# U2FHIDDevice_1.net
KiCad netlist of a schematic drawn in EAGLE
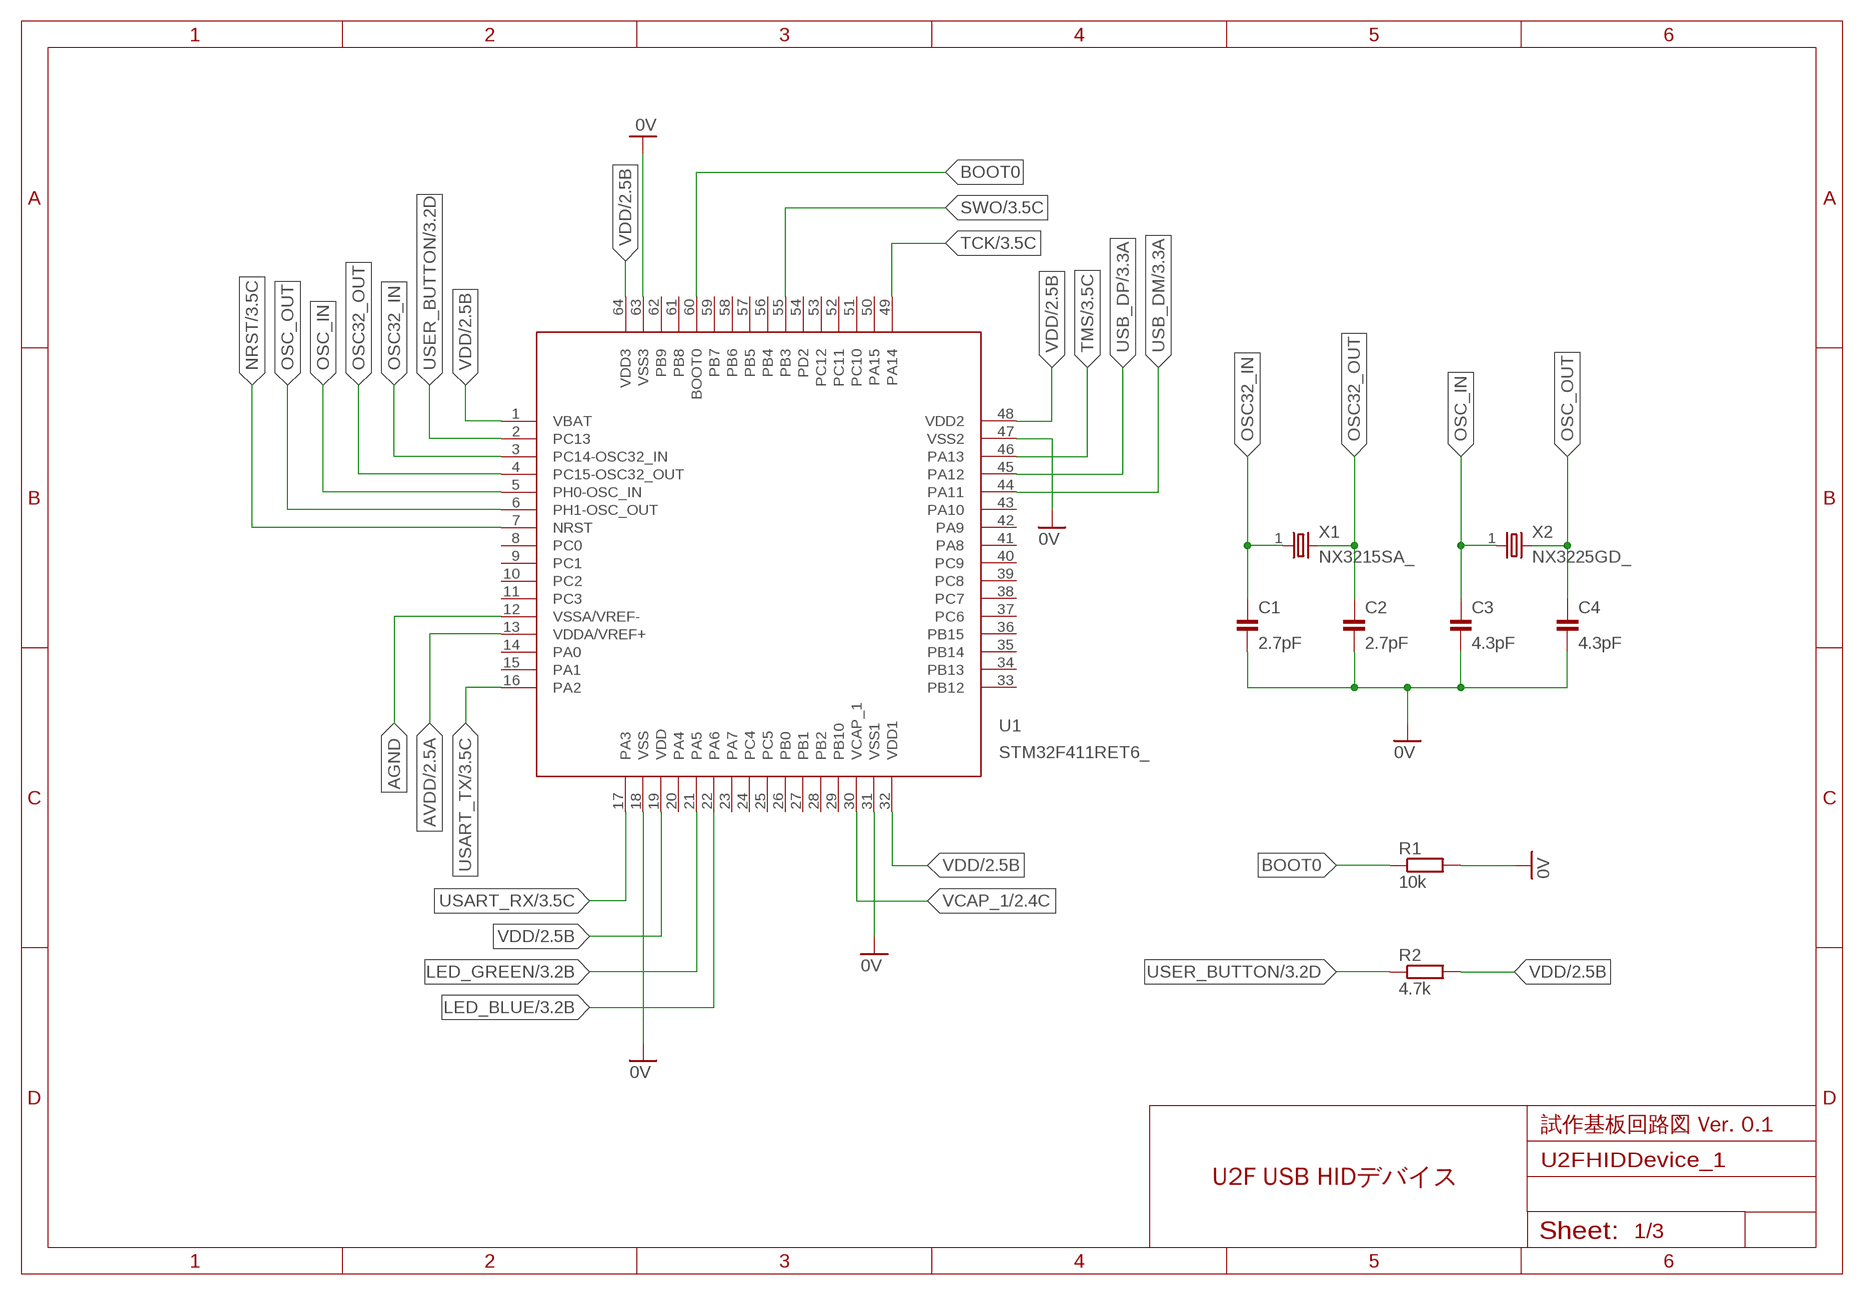
[diagram p0: schematic, sheet 1]
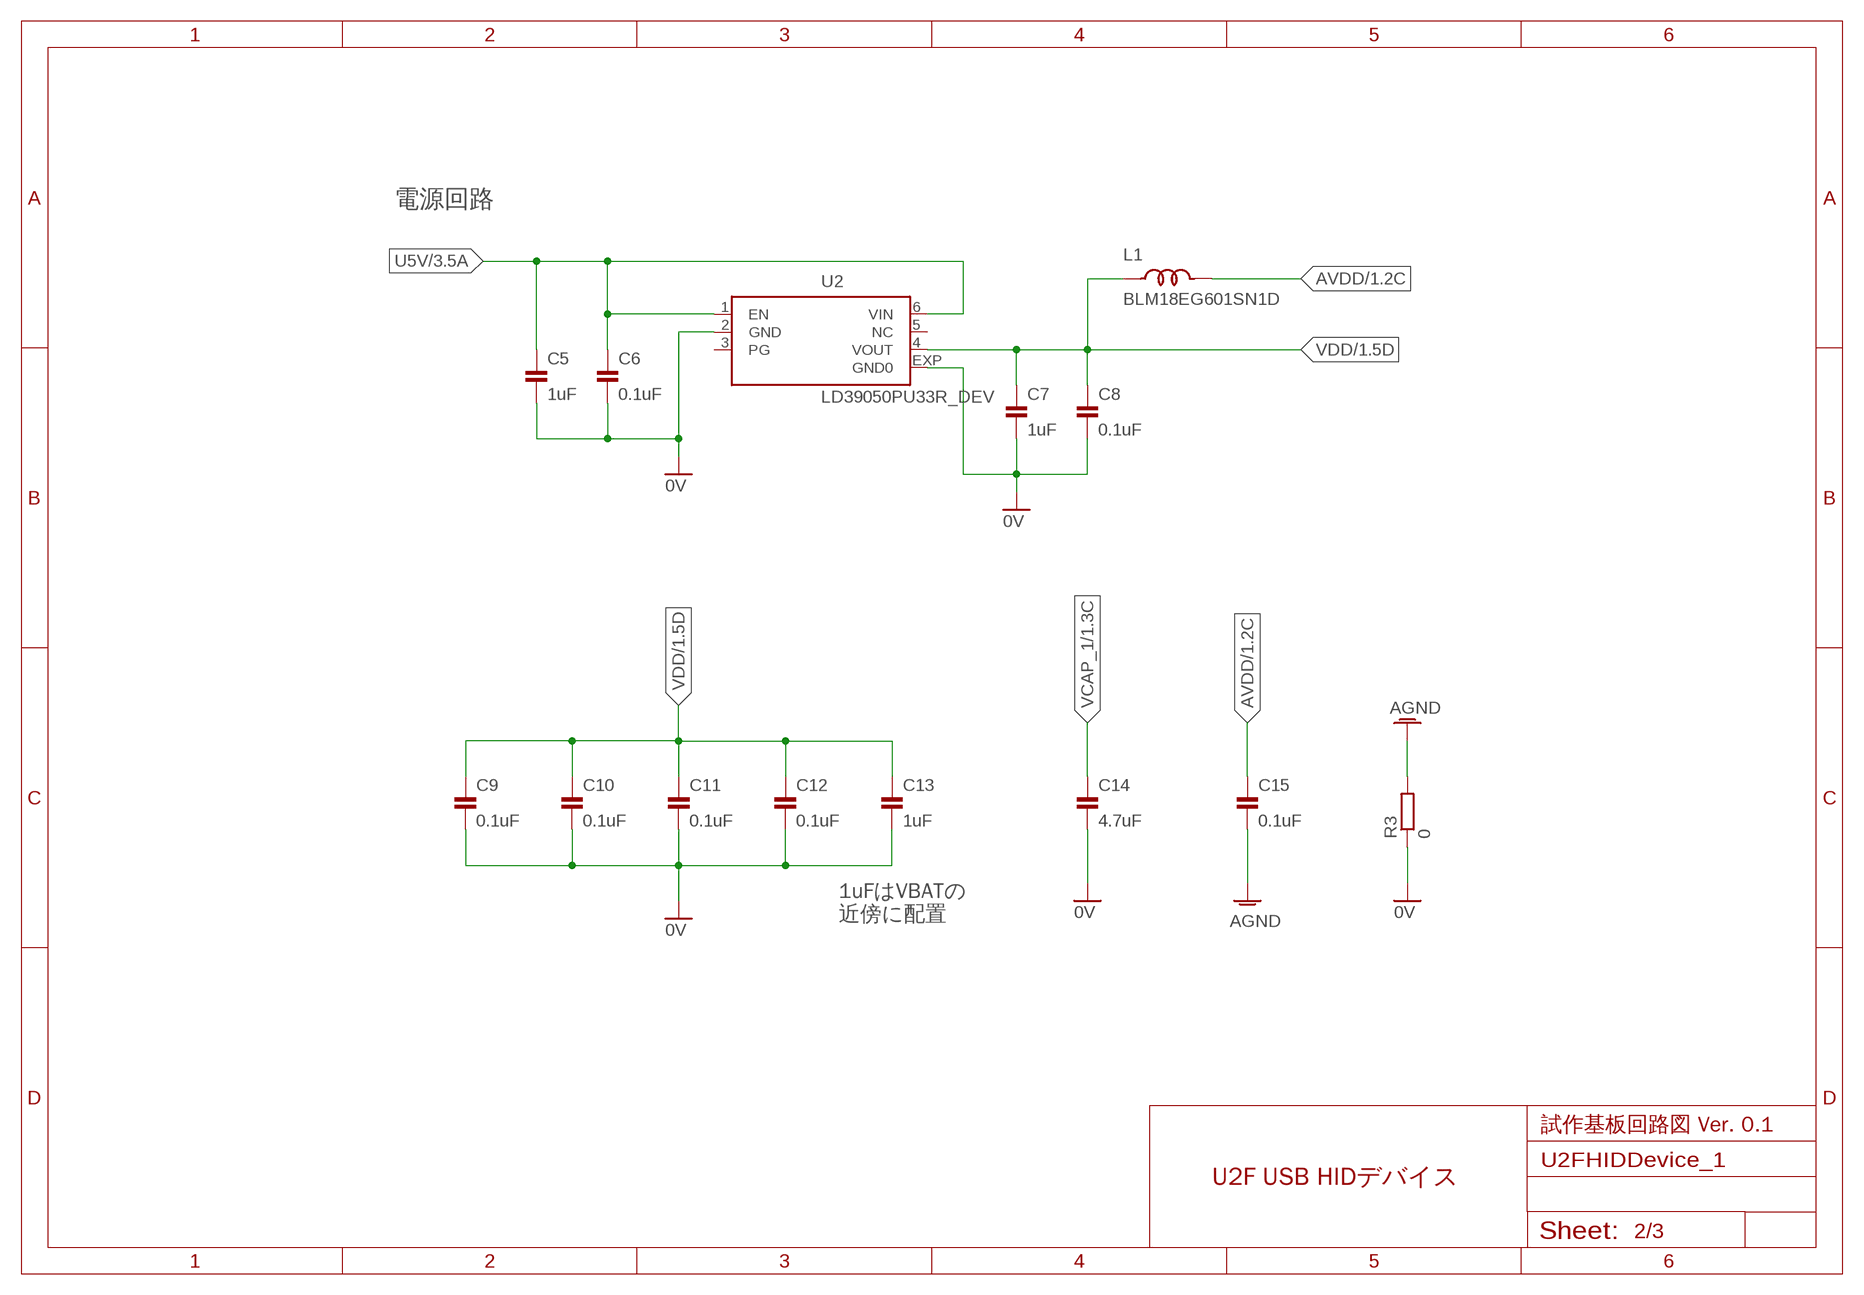
[diagram p1: schematic, sheet 2]
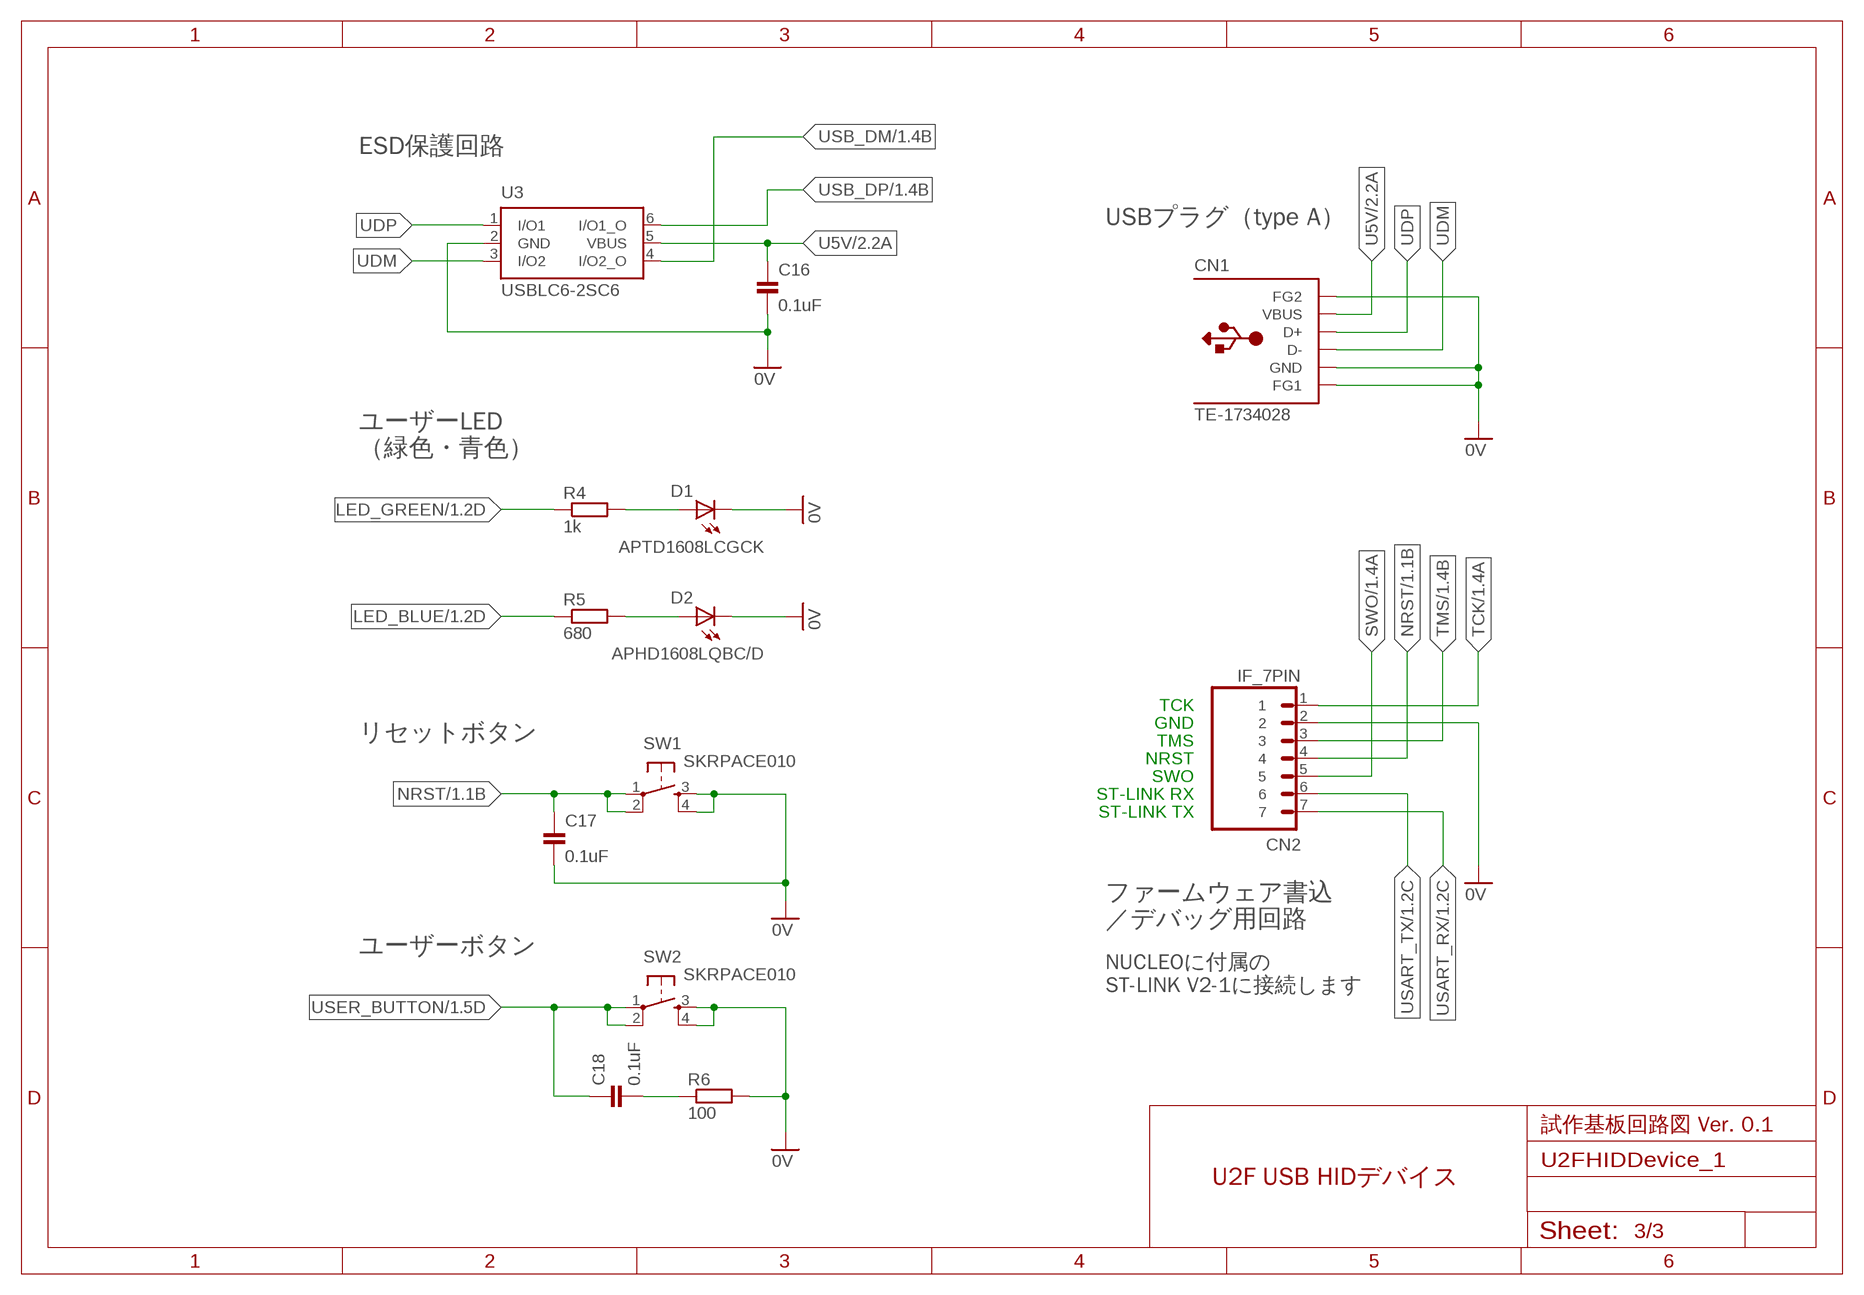
[diagram p2: schematic, sheet 3]

(export (version "E")
  (design (tool "Eeschema 10.0.6"))
  (components
    (comp (ref "C5")
      (value "1uF")
      (footprint "eagle-import:C0603K")
      (libsource (lib "eagle-import") (part "CAP_0603"))
    )
    (comp (ref "C6")
      (value "0.1uF")
      (footprint "eagle-import:C0603K")
      (libsource (lib "eagle-import") (part "CAP_0603"))
    )
    (comp (ref "C7")
      (value "1uF")
      (footprint "eagle-import:C0603K")
      (libsource (lib "eagle-import") (part "CAP_0603"))
    )
    (comp (ref "C8")
      (value "0.1uF")
      (footprint "eagle-import:C0603K")
      (libsource (lib "eagle-import") (part "CAP_0603"))
    )
    (comp (ref "C9")
      (value "0.1uF")
      (footprint "eagle-import:C0603K")
      (libsource (lib "eagle-import") (part "CAP_0603"))
    )
    (comp (ref "C10")
      (value "0.1uF")
      (footprint "eagle-import:C0603K")
      (libsource (lib "eagle-import") (part "CAP_0603"))
    )
    (comp (ref "C11")
      (value "0.1uF")
      (footprint "eagle-import:C0603K")
      (libsource (lib "eagle-import") (part "CAP_0603"))
    )
    (comp (ref "C12")
      (value "0.1uF")
      (footprint "eagle-import:C0603K")
      (libsource (lib "eagle-import") (part "CAP_0603"))
    )
    (comp (ref "C13")
      (value "1uF")
      (footprint "eagle-import:C0603K")
      (libsource (lib "eagle-import") (part "CAP_0603"))
    )
    (comp (ref "C14")
      (value "4.7uF")
      (footprint "eagle-import:C1206")
      (libsource (lib "eagle-import") (part "CAP_1206"))
    )
    (comp (ref "C15")
      (value "0.1uF")
      (footprint "eagle-import:C0603K")
      (libsource (lib "eagle-import") (part "CAP_0603"))
    )
    (comp (ref "L1")
      (value "BLM18EG601SN1D")
      (footprint "eagle-import:R0603")
      (libsource (lib "eagle-import") (part "BLM18EG601SN1D"))
    )
    (comp (ref "R3")
      (value "0")
      (footprint "eagle-import:R0603")
      (libsource (lib "eagle-import") (part "RESISTOR_0603"))
    )
    (comp (ref "U2")
      (value "LD39050PU33R_DEV")
      (footprint "eagle-import:DFN6-3X3_DEV")
      (libsource (lib "eagle-import") (part "LD39050PU33R_DEV"))
    )
    (comp (ref "C1")
      (value "2.7pF")
      (footprint "eagle-import:C0603K")
      (libsource (lib "eagle-import") (part "CAP_0603"))
    )
    (comp (ref "C2")
      (value "2.7pF")
      (footprint "eagle-import:C0603K")
      (libsource (lib "eagle-import") (part "CAP_0603"))
    )
    (comp (ref "C3")
      (value "4.3pF")
      (footprint "eagle-import:C0603K")
      (libsource (lib "eagle-import") (part "CAP_0603"))
    )
    (comp (ref "C4")
      (value "4.3pF")
      (footprint "eagle-import:C0603K")
      (libsource (lib "eagle-import") (part "CAP_0603"))
    )
    (comp (ref "R1")
      (value "10k")
      (footprint "eagle-import:R0603")
      (libsource (lib "eagle-import") (part "RESISTOR_0603"))
    )
    (comp (ref "R2")
      (value "4.7k")
      (footprint "eagle-import:R0603")
      (libsource (lib "eagle-import") (part "RESISTOR_0603"))
    )
    (comp (ref "U1")
      (value "STM32F411RET6_")
      (footprint "eagle-import:LQFP64-10X10_DEV")
      (libsource (lib "eagle-import") (part "STM32F411RET6_"))
    )
    (comp (ref "X1")
      (value "NX3215SA_")
      (footprint "eagle-import:NX3215_DEV")
      (libsource (lib "eagle-import") (part "NX3215SA_"))
    )
    (comp (ref "X2")
      (value "NX3225GD_")
      (footprint "eagle-import:NX3225_DEV")
      (libsource (lib "eagle-import") (part "NX3225GD_"))
    )
    (comp (ref "C16")
      (value "0.1uF")
      (footprint "eagle-import:C0603K")
      (libsource (lib "eagle-import") (part "CAP_0603"))
    )
    (comp (ref "C17")
      (value "0.1uF")
      (footprint "eagle-import:C0603K")
      (libsource (lib "eagle-import") (part "CAP_0603"))
    )
    (comp (ref "C18")
      (value "0.1uF")
      (footprint "eagle-import:C0603K")
      (libsource (lib "eagle-import") (part "CAP_0603"))
    )
    (comp (ref "CN1")
      (value "TE-1734028")
      (footprint "eagle-import:TE-1734028")
      (libsource (lib "eagle-import") (part "TE-1734028"))
    )
    (comp (ref "CN2")
      (value "IF_7PIN")
      (footprint "eagle-import:HEADER_7PIN")
      (libsource (lib "eagle-import") (part "IF_7PIN"))
    )
    (comp (ref "D1")
      (value "APTD1608LCGCK")
      (footprint "eagle-import:CHIPLED_0603")
      (libsource (lib "eagle-import") (part "APTD1608LCGCK"))
    )
    (comp (ref "D2")
      (value "APHD1608LQBC/D")
      (footprint "eagle-import:CHIPLED_0603")
      (libsource (lib "eagle-import") (part "APHD1608LQBC/D"))
    )
    (comp (ref "R4")
      (value "1k")
      (footprint "eagle-import:R0603")
      (libsource (lib "eagle-import") (part "RESISTOR_0603"))
    )
    (comp (ref "R5")
      (value "680")
      (footprint "eagle-import:R0603")
      (libsource (lib "eagle-import") (part "RESISTOR_0603"))
    )
    (comp (ref "R6")
      (value "100")
      (footprint "eagle-import:R0603")
      (libsource (lib "eagle-import") (part "RESISTOR_0603"))
    )
    (comp (ref "SW1")
      (value "SKRPACE010")
      (footprint "eagle-import:SKRPACE010")
      (libsource (lib "eagle-import") (part "SKRPACE010"))
    )
    (comp (ref "SW2")
      (value "SKRPACE010")
      (footprint "eagle-import:SKRPACE010")
      (libsource (lib "eagle-import") (part "SKRPACE010"))
    )
    (comp (ref "U3")
      (value "USBLC6-2SC6")
      (footprint "eagle-import:SOT23-6L")
      (libsource (lib "eagle-import") (part "USBLC6-2SC6"))
    )
  )
  (nets
    (net (code "1") (name "0V") (class "Default")
      (node (ref "C1") (pin "2") (pinfunction "2_2") (pintype "passive"))
      (node (ref "C10") (pin "2") (pinfunction "2_2") (pintype "passive"))
      (node (ref "C11") (pin "2") (pinfunction "2_2") (pintype "passive"))
      (node (ref "C12") (pin "2") (pinfunction "2_2") (pintype "passive"))
      (node (ref "C13") (pin "2") (pinfunction "2_2") (pintype "passive"))
      (node (ref "C14") (pin "2") (pinfunction "2_2") (pintype "passive"))
      (node (ref "C16") (pin "2") (pinfunction "2_2") (pintype "passive"))
      (node (ref "C17") (pin "2") (pinfunction "2_2") (pintype "passive"))
      (node (ref "C2") (pin "2") (pinfunction "2_2") (pintype "passive"))
      (node (ref "C3") (pin "2") (pinfunction "2_2") (pintype "passive"))
      (node (ref "C4") (pin "2") (pinfunction "2_2") (pintype "passive"))
      (node (ref "C5") (pin "2") (pinfunction "2_2") (pintype "passive"))
      (node (ref "C6") (pin "2") (pinfunction "2_2") (pintype "passive"))
      (node (ref "C7") (pin "2") (pinfunction "2_2") (pintype "passive"))
      (node (ref "C8") (pin "2") (pinfunction "2_2") (pintype "passive"))
      (node (ref "C9") (pin "2") (pinfunction "2_2") (pintype "passive"))
      (node (ref "CN1") (pin "FG1") (pinfunction "FG1_FG1") (pintype "passive"))
      (node (ref "CN1") (pin "FG2") (pinfunction "FG2_FG2") (pintype "passive"))
      (node (ref "CN1") (pin "P$4") (pinfunction "GND_P$4") (pintype "passive"))
      (node (ref "CN2") (pin "2") (pinfunction "2_2") (pintype "passive"))
      (node (ref "D1") (pin "C") (pinfunction "C_C") (pintype "passive"))
      (node (ref "D2") (pin "C") (pinfunction "C_C") (pintype "passive"))
      (node (ref "R1") (pin "2") (pinfunction "2_2") (pintype "passive"))
      (node (ref "R3") (pin "1") (pinfunction "1_1") (pintype "passive"))
      (node (ref "R6") (pin "2") (pinfunction "2_2") (pintype "passive"))
      (node (ref "SW1") (pin "3") (pinfunction "S_3") (pintype "passive"))
      (node (ref "SW1") (pin "4") (pinfunction "S1_4") (pintype "passive"))
      (node (ref "SW2") (pin "3") (pinfunction "S_3") (pintype "passive"))
      (node (ref "SW2") (pin "4") (pinfunction "S1_4") (pintype "passive"))
      (node (ref "U1") (pin "18") (pinfunction "VSS_18") (pintype "passive"))
      (node (ref "U1") (pin "31") (pinfunction "VSS1_31") (pintype "passive"))
      (node (ref "U1") (pin "47") (pinfunction "VSS2_47") (pintype "passive"))
      (node (ref "U1") (pin "63") (pinfunction "VSS3_63") (pintype "passive"))
      (node (ref "U2") (pin "2") (pinfunction "GND_2") (pintype "passive"))
      (node (ref "U2") (pin "EXP") (pinfunction "GND0_EXP") (pintype "passive"))
      (node (ref "U3") (pin "2") (pinfunction "GND_2") (pintype "passive"))
    )
    (net (code "2") (name "AGND") (class "Default")
      (node (ref "C15") (pin "2") (pinfunction "2_2") (pintype "passive"))
      (node (ref "R3") (pin "2") (pinfunction "2_2") (pintype "passive"))
      (node (ref "U1") (pin "12") (pinfunction "VSSA/VREF-_12") (pintype "passive"))
    )
    (net (code "3") (name "AVDD") (class "Default")
      (node (ref "C15") (pin "1") (pinfunction "1_1") (pintype "passive"))
      (node (ref "L1") (pin "2") (pinfunction "2_2") (pintype "passive"))
      (node (ref "U1") (pin "13") (pinfunction "VDDA/VREF+_13") (pintype "passive"))
    )
    (net (code "4") (name "BOOT0") (class "Default")
      (node (ref "R1") (pin "1") (pinfunction "1_1") (pintype "passive"))
      (node (ref "U1") (pin "60") (pinfunction "BOOT0_60") (pintype "bidirectional"))
    )
    (net (code "5") (name "LED_BLUE") (class "Default")
      (node (ref "R5") (pin "1") (pinfunction "1_1") (pintype "passive"))
      (node (ref "U1") (pin "22") (pinfunction "PA6_22") (pintype "bidirectional"))
    )
    (net (code "6") (name "LED_GREEN") (class "Default")
      (node (ref "R4") (pin "1") (pinfunction "1_1") (pintype "passive"))
      (node (ref "U1") (pin "21") (pinfunction "PA5_21") (pintype "bidirectional"))
    )
    (net (code "7") (name "NRST") (class "Default")
      (node (ref "C17") (pin "1") (pinfunction "1_1") (pintype "passive"))
      (node (ref "CN2") (pin "4") (pinfunction "4_4") (pintype "passive"))
      (node (ref "SW1") (pin "1") (pinfunction "P_1") (pintype "passive"))
      (node (ref "SW1") (pin "2") (pinfunction "P1_2") (pintype "passive"))
      (node (ref "U1") (pin "7") (pinfunction "NRST_7") (pintype "bidirectional"))
    )
    (net (code "8") (name "Net-(C18-Pad2)") (class "Default")
      (node (ref "C18") (pin "2") (pinfunction "2_2") (pintype "passive"))
      (node (ref "R6") (pin "1") (pinfunction "1_1") (pintype "passive"))
    )
    (net (code "9") (name "Net-(D1-PadA)") (class "Default")
      (node (ref "D1") (pin "A") (pinfunction "A_A") (pintype "passive"))
      (node (ref "R4") (pin "2") (pinfunction "2_2") (pintype "passive"))
    )
    (net (code "10") (name "Net-(D2-PadA)") (class "Default")
      (node (ref "D2") (pin "A") (pinfunction "A_A") (pintype "passive"))
      (node (ref "R5") (pin "2") (pinfunction "2_2") (pintype "passive"))
    )
    (net (code "11") (name "OSC32_IN") (class "Default")
      (node (ref "C1") (pin "1") (pinfunction "1_1") (pintype "passive"))
      (node (ref "U1") (pin "3") (pinfunction "PC14-OSC32_IN_3") (pintype "bidirectional"))
      (node (ref "X1") (pin "1") (pinfunction "1_1") (pintype "passive"))
    )
    (net (code "12") (name "OSC32_OUT") (class "Default")
      (node (ref "C2") (pin "1") (pinfunction "1_1") (pintype "passive"))
      (node (ref "U1") (pin "4") (pinfunction "PC15-OSC32_OUT_4") (pintype "bidirectional"))
      (node (ref "X1") (pin "2") (pinfunction "2_2") (pintype "passive"))
    )
    (net (code "13") (name "OSC_IN") (class "Default")
      (node (ref "C3") (pin "1") (pinfunction "1_1") (pintype "passive"))
      (node (ref "U1") (pin "5") (pinfunction "PH0-OSC_IN_5") (pintype "bidirectional"))
      (node (ref "X2") (pin "1") (pinfunction "1_1") (pintype "passive"))
    )
    (net (code "14") (name "OSC_OUT") (class "Default")
      (node (ref "C4") (pin "1") (pinfunction "1_1") (pintype "passive"))
      (node (ref "U1") (pin "6") (pinfunction "PH1-OSC_OUT_6") (pintype "bidirectional"))
      (node (ref "X2") (pin "2") (pinfunction "2_2") (pintype "passive"))
    )
    (net (code "15") (name "SWO") (class "Default")
      (node (ref "CN2") (pin "5") (pinfunction "5_5") (pintype "passive"))
      (node (ref "U1") (pin "55") (pinfunction "PB3_55") (pintype "bidirectional"))
    )
    (net (code "16") (name "TCK") (class "Default")
      (node (ref "CN2") (pin "1") (pinfunction "1_1") (pintype "passive"))
      (node (ref "U1") (pin "49") (pinfunction "PA14_49") (pintype "bidirectional"))
    )
    (net (code "17") (name "TMS") (class "Default")
      (node (ref "CN2") (pin "3") (pinfunction "3_3") (pintype "passive"))
      (node (ref "U1") (pin "46") (pinfunction "PA13_46") (pintype "bidirectional"))
    )
    (net (code "18") (name "U5V") (class "Default")
      (node (ref "C16") (pin "1") (pinfunction "1_1") (pintype "passive"))
      (node (ref "C5") (pin "1") (pinfunction "1_1") (pintype "passive"))
      (node (ref "C6") (pin "1") (pinfunction "1_1") (pintype "passive"))
      (node (ref "CN1") (pin "P$1") (pinfunction "VBUS_P$1") (pintype "passive"))
      (node (ref "U2") (pin "1") (pinfunction "EN_1") (pintype "bidirectional"))
      (node (ref "U2") (pin "6") (pinfunction "VIN_6") (pintype "passive"))
      (node (ref "U3") (pin "5") (pinfunction "VBUS_5") (pintype "passive"))
    )
    (net (code "19") (name "UDM") (class "Default")
      (node (ref "CN1") (pin "P$2") (pinfunction "D-_P$2") (pintype "bidirectional"))
      (node (ref "U3") (pin "3") (pinfunction "I/O2_3") (pintype "bidirectional"))
    )
    (net (code "20") (name "UDP") (class "Default")
      (node (ref "CN1") (pin "P$3") (pinfunction "D+_P$3") (pintype "bidirectional"))
      (node (ref "U3") (pin "1") (pinfunction "I/O1_1") (pintype "bidirectional"))
    )
    (net (code "21") (name "USART_RX") (class "Default")
      (node (ref "CN2") (pin "7") (pinfunction "7_7") (pintype "passive"))
      (node (ref "U1") (pin "17") (pinfunction "PA3_17") (pintype "bidirectional"))
    )
    (net (code "22") (name "USART_TX") (class "Default")
      (node (ref "CN2") (pin "6") (pinfunction "6_6") (pintype "passive"))
      (node (ref "U1") (pin "16") (pinfunction "PA2_16") (pintype "bidirectional"))
    )
    (net (code "23") (name "USB_DM") (class "Default")
      (node (ref "U1") (pin "44") (pinfunction "PA11_44") (pintype "bidirectional"))
      (node (ref "U3") (pin "4") (pinfunction "I/O2_O_4") (pintype "bidirectional"))
    )
    (net (code "24") (name "USB_DP") (class "Default")
      (node (ref "U1") (pin "45") (pinfunction "PA12_45") (pintype "bidirectional"))
      (node (ref "U3") (pin "6") (pinfunction "I/O1_O_6") (pintype "bidirectional"))
    )
    (net (code "25") (name "USER_BUTTON") (class "Default")
      (node (ref "C18") (pin "1") (pinfunction "1_1") (pintype "passive"))
      (node (ref "R2") (pin "1") (pinfunction "1_1") (pintype "passive"))
      (node (ref "SW2") (pin "1") (pinfunction "P_1") (pintype "passive"))
      (node (ref "SW2") (pin "2") (pinfunction "P1_2") (pintype "passive"))
      (node (ref "U1") (pin "2") (pinfunction "PC13_2") (pintype "bidirectional"))
    )
    (net (code "26") (name "VCAP_1") (class "Default")
      (node (ref "C14") (pin "1") (pinfunction "1_1") (pintype "passive"))
      (node (ref "U1") (pin "30") (pinfunction "VCAP_1_30") (pintype "passive"))
    )
    (net (code "27") (name "VDD") (class "Default")
      (node (ref "C10") (pin "1") (pinfunction "1_1") (pintype "passive"))
      (node (ref "C11") (pin "1") (pinfunction "1_1") (pintype "passive"))
      (node (ref "C12") (pin "1") (pinfunction "1_1") (pintype "passive"))
      (node (ref "C13") (pin "1") (pinfunction "1_1") (pintype "passive"))
      (node (ref "C7") (pin "1") (pinfunction "1_1") (pintype "passive"))
      (node (ref "C8") (pin "1") (pinfunction "1_1") (pintype "passive"))
      (node (ref "C9") (pin "1") (pinfunction "1_1") (pintype "passive"))
      (node (ref "L1") (pin "1") (pinfunction "1_1") (pintype "passive"))
      (node (ref "R2") (pin "2") (pinfunction "2_2") (pintype "passive"))
      (node (ref "U1") (pin "1") (pinfunction "VBAT_1") (pintype "passive"))
      (node (ref "U1") (pin "19") (pinfunction "VDD_19") (pintype "passive"))
      (node (ref "U1") (pin "32") (pinfunction "VDD1_32") (pintype "passive"))
      (node (ref "U1") (pin "48") (pinfunction "VDD2_48") (pintype "passive"))
      (node (ref "U1") (pin "64") (pinfunction "VDD3_64") (pintype "passive"))
      (node (ref "U2") (pin "4") (pinfunction "VOUT_4") (pintype "passive"))
    )
    (net (code "28") (name "unconnected-(U1-PA0-Pad14)") (class "Default")
      (node (ref "U1") (pin "14") (pinfunction "PA0_14") (pintype "bidirectional"))
    )
    (net (code "29") (name "unconnected-(U1-PA1-Pad15)") (class "Default")
      (node (ref "U1") (pin "15") (pinfunction "PA1_15") (pintype "bidirectional"))
    )
    (net (code "30") (name "unconnected-(U1-PA4-Pad20)") (class "Default")
      (node (ref "U1") (pin "20") (pinfunction "PA4_20") (pintype "bidirectional"))
    )
    (net (code "31") (name "unconnected-(U1-PA7-Pad23)") (class "Default")
      (node (ref "U1") (pin "23") (pinfunction "PA7_23") (pintype "bidirectional"))
    )
    (net (code "32") (name "unconnected-(U1-PA8-Pad41)") (class "Default")
      (node (ref "U1") (pin "41") (pinfunction "PA8_41") (pintype "bidirectional"))
    )
    (net (code "33") (name "unconnected-(U1-PA9-Pad42)") (class "Default")
      (node (ref "U1") (pin "42") (pinfunction "PA9_42") (pintype "bidirectional"))
    )
    (net (code "34") (name "unconnected-(U1-PA10-Pad43)") (class "Default")
      (node (ref "U1") (pin "43") (pinfunction "PA10_43") (pintype "bidirectional"))
    )
    (net (code "35") (name "unconnected-(U1-PA15-Pad50)") (class "Default")
      (node (ref "U1") (pin "50") (pinfunction "PA15_50") (pintype "bidirectional"))
    )
    (net (code "36") (name "unconnected-(U1-PB0-Pad26)") (class "Default")
      (node (ref "U1") (pin "26") (pinfunction "PB0_26") (pintype "bidirectional"))
    )
    (net (code "37") (name "unconnected-(U1-PB1-Pad27)") (class "Default")
      (node (ref "U1") (pin "27") (pinfunction "PB1_27") (pintype "bidirectional"))
    )
    (net (code "38") (name "unconnected-(U1-PB2-Pad28)") (class "Default")
      (node (ref "U1") (pin "28") (pinfunction "PB2_28") (pintype "bidirectional"))
    )
    (net (code "39") (name "unconnected-(U1-PB4-Pad56)") (class "Default")
      (node (ref "U1") (pin "56") (pinfunction "PB4_56") (pintype "bidirectional"))
    )
    (net (code "40") (name "unconnected-(U1-PB5-Pad57)") (class "Default")
      (node (ref "U1") (pin "57") (pinfunction "PB5_57") (pintype "bidirectional"))
    )
    (net (code "41") (name "unconnected-(U1-PB6-Pad58)") (class "Default")
      (node (ref "U1") (pin "58") (pinfunction "PB6_58") (pintype "bidirectional"))
    )
    (net (code "42") (name "unconnected-(U1-PB7-Pad59)") (class "Default")
      (node (ref "U1") (pin "59") (pinfunction "PB7_59") (pintype "bidirectional"))
    )
    (net (code "43") (name "unconnected-(U1-PB8-Pad61)") (class "Default")
      (node (ref "U1") (pin "61") (pinfunction "PB8_61") (pintype "bidirectional"))
    )
    (net (code "44") (name "unconnected-(U1-PB9-Pad62)") (class "Default")
      (node (ref "U1") (pin "62") (pinfunction "PB9_62") (pintype "bidirectional"))
    )
    (net (code "45") (name "unconnected-(U1-PB10-Pad29)") (class "Default")
      (node (ref "U1") (pin "29") (pinfunction "PB10_29") (pintype "bidirectional"))
    )
    (net (code "46") (name "unconnected-(U1-PB12-Pad33)") (class "Default")
      (node (ref "U1") (pin "33") (pinfunction "PB12_33") (pintype "bidirectional"))
    )
    (net (code "47") (name "unconnected-(U1-PB13-Pad34)") (class "Default")
      (node (ref "U1") (pin "34") (pinfunction "PB13_34") (pintype "bidirectional"))
    )
    (net (code "48") (name "unconnected-(U1-PB14-Pad35)") (class "Default")
      (node (ref "U1") (pin "35") (pinfunction "PB14_35") (pintype "bidirectional"))
    )
    (net (code "49") (name "unconnected-(U1-PB15-Pad36)") (class "Default")
      (node (ref "U1") (pin "36") (pinfunction "PB15_36") (pintype "bidirectional"))
    )
    (net (code "50") (name "unconnected-(U1-PC0-Pad8)") (class "Default")
      (node (ref "U1") (pin "8") (pinfunction "PC0_8") (pintype "bidirectional"))
    )
    (net (code "51") (name "unconnected-(U1-PC1-Pad9)") (class "Default")
      (node (ref "U1") (pin "9") (pinfunction "PC1_9") (pintype "bidirectional"))
    )
    (net (code "52") (name "unconnected-(U1-PC2-Pad10)") (class "Default")
      (node (ref "U1") (pin "10") (pinfunction "PC2_10") (pintype "bidirectional"))
    )
    (net (code "53") (name "unconnected-(U1-PC3-Pad11)") (class "Default")
      (node (ref "U1") (pin "11") (pinfunction "PC3_11") (pintype "bidirectional"))
    )
    (net (code "54") (name "unconnected-(U1-PC4-Pad24)") (class "Default")
      (node (ref "U1") (pin "24") (pinfunction "PC4_24") (pintype "bidirectional"))
    )
    (net (code "55") (name "unconnected-(U1-PC5-Pad25)") (class "Default")
      (node (ref "U1") (pin "25") (pinfunction "PC5_25") (pintype "bidirectional"))
    )
    (net (code "56") (name "unconnected-(U1-PC6-Pad37)") (class "Default")
      (node (ref "U1") (pin "37") (pinfunction "PC6_37") (pintype "bidirectional"))
    )
    (net (code "57") (name "unconnected-(U1-PC7-Pad38)") (class "Default")
      (node (ref "U1") (pin "38") (pinfunction "PC7_38") (pintype "bidirectional"))
    )
    (net (code "58") (name "unconnected-(U1-PC8-Pad39)") (class "Default")
      (node (ref "U1") (pin "39") (pinfunction "PC8_39") (pintype "bidirectional"))
    )
    (net (code "59") (name "unconnected-(U1-PC9-Pad40)") (class "Default")
      (node (ref "U1") (pin "40") (pinfunction "PC9_40") (pintype "bidirectional"))
    )
    (net (code "60") (name "unconnected-(U1-PC10-Pad51)") (class "Default")
      (node (ref "U1") (pin "51") (pinfunction "PC10_51") (pintype "bidirectional"))
    )
    (net (code "61") (name "unconnected-(U1-PC11-Pad52)") (class "Default")
      (node (ref "U1") (pin "52") (pinfunction "PC11_52") (pintype "bidirectional"))
    )
    (net (code "62") (name "unconnected-(U1-PC12-Pad53)") (class "Default")
      (node (ref "U1") (pin "53") (pinfunction "PC12_53") (pintype "bidirectional"))
    )
    (net (code "63") (name "unconnected-(U1-PD2-Pad54)") (class "Default")
      (node (ref "U1") (pin "54") (pinfunction "PD2_54") (pintype "bidirectional"))
    )
    (net (code "64") (name "unconnected-(U2-NC-Pad5)") (class "Default")
      (node (ref "U2") (pin "5") (pinfunction "NC_5") (pintype "no_connect"))
    )
    (net (code "65") (name "unconnected-(U2-PG-Pad3)") (class "Default")
      (node (ref "U2") (pin "3") (pinfunction "PG_3") (pintype "bidirectional"))
    )
  )
)
